# me433.net
KiCad netlist of a schematic drawn in EAGLE
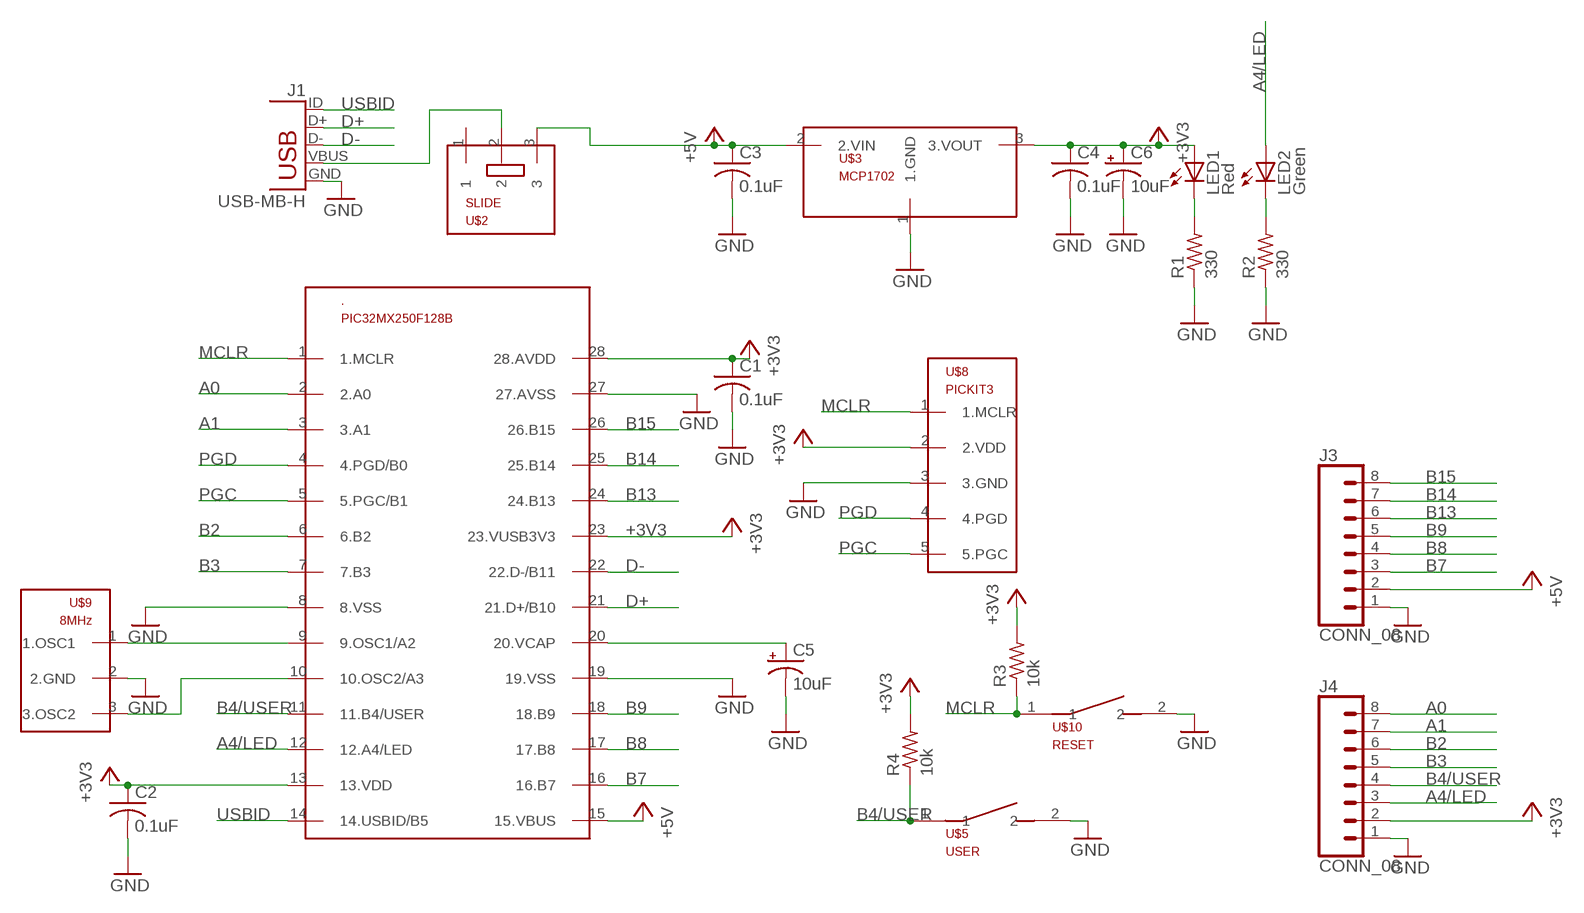
[diagram p0: schematic, sheet 1]

(export (version "E")
  (design (tool "Eeschema 10.0.6"))
  (components
    (comp (ref ".")
      (value "PIC32MX250F128B")
      (footprint "eagle-import:DIL28-3")
      (libsource (lib "eagle-import") (part "PIC32MX250F128B"))
    )
    (comp (ref "C1")
      (value "0.1uF")
      (footprint "eagle-import:C025-025X050")
      (libsource (lib "eagle-import") (part "C-US025-025X050"))
    )
    (comp (ref "C2")
      (value "0.1uF")
      (footprint "eagle-import:C025-025X050")
      (libsource (lib "eagle-import") (part "C-US025-025X050"))
    )
    (comp (ref "C3")
      (value "0.1uF")
      (footprint "eagle-import:C025-025X050")
      (libsource (lib "eagle-import") (part "C-US025-025X050"))
    )
    (comp (ref "C4")
      (value "0.1uF")
      (footprint "eagle-import:C025-025X050")
      (libsource (lib "eagle-import") (part "C-US025-025X050"))
    )
    (comp (ref "C5")
      (value "10uF")
      (footprint "eagle-import:B45181B")
      (libsource (lib "eagle-import") (part "CPOL-USB45181B"))
    )
    (comp (ref "C6")
      (value "10uF")
      (footprint "eagle-import:B45181B")
      (libsource (lib "eagle-import") (part "CPOL-USB45181B"))
    )
    (comp (ref "J1")
      (value "USB-MB-H")
      (footprint "eagle-import:USB-MB-H")
      (libsource (lib "eagle-import") (part "USB-MB-H"))
    )
    (comp (ref "J3")
      (value "CONN_08")
      (footprint "eagle-import:1X08")
      (libsource (lib "eagle-import") (part "CONN_08"))
    )
    (comp (ref "J4")
      (value "CONN_08")
      (footprint "eagle-import:1X08")
      (libsource (lib "eagle-import") (part "CONN_08"))
    )
    (comp (ref "LED1")
      (value "Red")
      (footprint "eagle-import:LED3MM")
      (libsource (lib "eagle-import") (part "LED3MM"))
    )
    (comp (ref "LED2")
      (value "Green")
      (footprint "eagle-import:LED3MM")
      (libsource (lib "eagle-import") (part "LED3MM"))
    )
    (comp (ref "R1")
      (value "330")
      (footprint "eagle-import:0207_10")
      (libsource (lib "eagle-import") (part "R-US_0207/10"))
    )
    (comp (ref "R2")
      (value "330")
      (footprint "eagle-import:0207_10")
      (libsource (lib "eagle-import") (part "R-US_0207/10"))
    )
    (comp (ref "R3")
      (value "10k")
      (footprint "eagle-import:0207_10")
      (libsource (lib "eagle-import") (part "R-US_0207/10"))
    )
    (comp (ref "R4")
      (value "10k")
      (footprint "eagle-import:0207_10")
      (libsource (lib "eagle-import") (part "R-US_0207/10"))
    )
    (comp (ref "U$2")
      (value "SLIDE")
      (footprint "eagle-import:SLIDE")
      (libsource (lib "eagle-import") (part "SLIDE"))
    )
    (comp (ref "U$3")
      (value "MCP1702")
      (footprint "eagle-import:TO92")
      (libsource (lib "eagle-import") (part "MCP1702"))
    )
    (comp (ref "U$5")
      (value "USER")
      (footprint "eagle-import:PB")
      (libsource (lib "eagle-import") (part "PB"))
    )
    (comp (ref "U$8")
      (value "PICKIT3")
      (footprint "eagle-import:1X05")
      (libsource (lib "eagle-import") (part "PICKIT3"))
    )
    (comp (ref "U$9")
      (value "8MHz")
      (footprint "eagle-import:OSC")
      (libsource (lib "eagle-import") (part "OSC"))
    )
    (comp (ref "U$10")
      (value "RESET")
      (footprint "eagle-import:PB")
      (libsource (lib "eagle-import") (part "PB"))
    )
  )
  (nets
    (net (code "1") (name "+3V3") (class "Default")
      (node (ref ".") (pin "13") (pinfunction "13.VDD_13") (pintype "bidirectional"))
      (node (ref ".") (pin "23") (pinfunction "23.VUSB3V3_23") (pintype "bidirectional"))
      (node (ref ".") (pin "28") (pinfunction "28.AVDD_28") (pintype "bidirectional"))
      (node (ref "C1") (pin "1") (pinfunction "1_1") (pintype "passive"))
      (node (ref "C2") (pin "1") (pinfunction "1_1") (pintype "passive"))
      (node (ref "C4") (pin "1") (pinfunction "1_1") (pintype "passive"))
      (node (ref "C6") (pin "+") (pinfunction "+_+") (pintype "passive"))
      (node (ref "J4") (pin "2") (pinfunction "2_2") (pintype "passive"))
      (node (ref "LED1") (pin "A") (pinfunction "A_A") (pintype "passive"))
      (node (ref "R3") (pin "2") (pinfunction "2_2") (pintype "passive"))
      (node (ref "R4") (pin "2") (pinfunction "2_2") (pintype "passive"))
      (node (ref "U$3") (pin "3") (pinfunction "3.VOUT_3") (pintype "bidirectional"))
      (node (ref "U$8") (pin "2") (pinfunction "2.VDD_2") (pintype "bidirectional"))
    )
    (net (code "2") (name "+5V") (class "Default")
      (node (ref ".") (pin "15") (pinfunction "15.VBUS_15") (pintype "bidirectional"))
      (node (ref "C3") (pin "1") (pinfunction "1_1") (pintype "passive"))
      (node (ref "J3") (pin "2") (pinfunction "2_2") (pintype "passive"))
      (node (ref "U$2") (pin "3") (pinfunction "3_3") (pintype "bidirectional"))
      (node (ref "U$3") (pin "2") (pinfunction "2.VIN_2") (pintype "bidirectional"))
    )
    (net (code "3") (name "/A0") (class "Default")
      (node (ref ".") (pin "2") (pinfunction "2.A0_2") (pintype "bidirectional"))
      (node (ref "J4") (pin "8") (pinfunction "8_8") (pintype "passive"))
    )
    (net (code "4") (name "/A1") (class "Default")
      (node (ref ".") (pin "3") (pinfunction "3.A1_3") (pintype "bidirectional"))
      (node (ref "J4") (pin "7") (pinfunction "7_7") (pintype "passive"))
    )
    (net (code "5") (name "/A4{slash}LED") (class "Default")
      (node (ref ".") (pin "12") (pinfunction "12.A4/LED_12") (pintype "bidirectional"))
      (node (ref "J4") (pin "3") (pinfunction "3_3") (pintype "passive"))
      (node (ref "LED2") (pin "A") (pinfunction "A_A") (pintype "passive"))
    )
    (net (code "6") (name "/B2") (class "Default")
      (node (ref ".") (pin "6") (pinfunction "6.B2_6") (pintype "bidirectional"))
      (node (ref "J4") (pin "6") (pinfunction "6_6") (pintype "passive"))
    )
    (net (code "7") (name "/B3") (class "Default")
      (node (ref ".") (pin "7") (pinfunction "7.B3_7") (pintype "bidirectional"))
      (node (ref "J4") (pin "5") (pinfunction "5_5") (pintype "passive"))
    )
    (net (code "8") (name "/B4{slash}USER") (class "Default")
      (node (ref ".") (pin "11") (pinfunction "11.B4/USER_11") (pintype "bidirectional"))
      (node (ref "J4") (pin "4") (pinfunction "4_4") (pintype "passive"))
      (node (ref "R4") (pin "1") (pinfunction "1_1") (pintype "passive"))
      (node (ref "U$5") (pin "1") (pinfunction "1_1") (pintype "bidirectional"))
    )
    (net (code "9") (name "/B7") (class "Default")
      (node (ref ".") (pin "16") (pinfunction "16.B7_16") (pintype "bidirectional"))
      (node (ref "J3") (pin "3") (pinfunction "3_3") (pintype "passive"))
    )
    (net (code "10") (name "/B8") (class "Default")
      (node (ref ".") (pin "17") (pinfunction "17.B8_17") (pintype "bidirectional"))
      (node (ref "J3") (pin "4") (pinfunction "4_4") (pintype "passive"))
    )
    (net (code "11") (name "/B9") (class "Default")
      (node (ref ".") (pin "18") (pinfunction "18.B9_18") (pintype "bidirectional"))
      (node (ref "J3") (pin "5") (pinfunction "5_5") (pintype "passive"))
    )
    (net (code "12") (name "/B13") (class "Default")
      (node (ref ".") (pin "24") (pinfunction "24.B13_24") (pintype "bidirectional"))
      (node (ref "J3") (pin "6") (pinfunction "6_6") (pintype "passive"))
    )
    (net (code "13") (name "/B14") (class "Default")
      (node (ref ".") (pin "25") (pinfunction "25.B14_25") (pintype "bidirectional"))
      (node (ref "J3") (pin "7") (pinfunction "7_7") (pintype "passive"))
    )
    (net (code "14") (name "/B15") (class "Default")
      (node (ref ".") (pin "26") (pinfunction "26.B15_26") (pintype "bidirectional"))
      (node (ref "J3") (pin "8") (pinfunction "8_8") (pintype "passive"))
    )
    (net (code "15") (name "/D+") (class "Default")
      (node (ref ".") (pin "21") (pinfunction "21.D+/B10_21") (pintype "bidirectional"))
      (node (ref "J1") (pin "D+") (pinfunction "D+_D+") (pintype "bidirectional"))
    )
    (net (code "16") (name "/D-") (class "Default")
      (node (ref ".") (pin "22") (pinfunction "22.D-/B11_22") (pintype "bidirectional"))
      (node (ref "J1") (pin "D-") (pinfunction "D-_D-") (pintype "bidirectional"))
    )
    (net (code "17") (name "/MCLR") (class "Default")
      (node (ref ".") (pin "1") (pinfunction "1.MCLR_1") (pintype "bidirectional"))
      (node (ref "R3") (pin "1") (pinfunction "1_1") (pintype "passive"))
      (node (ref "U$10") (pin "1") (pinfunction "1_1") (pintype "bidirectional"))
      (node (ref "U$8") (pin "1") (pinfunction "1.MCLR_1") (pintype "bidirectional"))
    )
    (net (code "18") (name "/PGC") (class "Default")
      (node (ref ".") (pin "5") (pinfunction "5.PGC/B1_5") (pintype "bidirectional"))
      (node (ref "U$8") (pin "5") (pinfunction "5.PGC_5") (pintype "bidirectional"))
    )
    (net (code "19") (name "/PGD") (class "Default")
      (node (ref ".") (pin "4") (pinfunction "4.PGD/B0_4") (pintype "bidirectional"))
      (node (ref "U$8") (pin "4") (pinfunction "4.PGD_4") (pintype "bidirectional"))
    )
    (net (code "20") (name "/USBID") (class "Default")
      (node (ref ".") (pin "14") (pinfunction "14.USBID/B5_14") (pintype "bidirectional"))
      (node (ref "J1") (pin "ID") (pinfunction "ID_ID") (pintype "bidirectional"))
    )
    (net (code "21") (name "GND") (class "Default")
      (node (ref ".") (pin "19") (pinfunction "19.VSS_19") (pintype "bidirectional"))
      (node (ref ".") (pin "27") (pinfunction "27.AVSS_27") (pintype "bidirectional"))
      (node (ref ".") (pin "8") (pinfunction "8.VSS_8") (pintype "bidirectional"))
      (node (ref "C1") (pin "2") (pinfunction "2_2") (pintype "passive"))
      (node (ref "C2") (pin "2") (pinfunction "2_2") (pintype "passive"))
      (node (ref "C3") (pin "2") (pinfunction "2_2") (pintype "passive"))
      (node (ref "C4") (pin "2") (pinfunction "2_2") (pintype "passive"))
      (node (ref "C5") (pin "-") (pinfunction "-_-") (pintype "passive"))
      (node (ref "C6") (pin "-") (pinfunction "-_-") (pintype "passive"))
      (node (ref "J1") (pin "GND") (pinfunction "GND_GND") (pintype "bidirectional"))
      (node (ref "J3") (pin "1") (pinfunction "1_1") (pintype "passive"))
      (node (ref "J4") (pin "1") (pinfunction "1_1") (pintype "passive"))
      (node (ref "R1") (pin "1") (pinfunction "1_1") (pintype "passive"))
      (node (ref "R2") (pin "1") (pinfunction "1_1") (pintype "passive"))
      (node (ref "U$10") (pin "2") (pinfunction "2_2") (pintype "bidirectional"))
      (node (ref "U$3") (pin "1") (pinfunction "1.GND_1") (pintype "bidirectional"))
      (node (ref "U$5") (pin "2") (pinfunction "2_2") (pintype "bidirectional"))
      (node (ref "U$8") (pin "3") (pinfunction "3.GND_3") (pintype "bidirectional"))
      (node (ref "U$9") (pin "2") (pinfunction "2.GND_2") (pintype "bidirectional"))
    )
    (net (code "22") (name "Net-(.-9.OSC1{slash}A2)") (class "Default")
      (node (ref ".") (pin "9") (pinfunction "9.OSC1/A2_9") (pintype "bidirectional"))
      (node (ref "U$9") (pin "1") (pinfunction "1.OSC1_1") (pintype "bidirectional"))
    )
    (net (code "23") (name "Net-(.-10.OSC2{slash}A3)") (class "Default")
      (node (ref ".") (pin "10") (pinfunction "10.OSC2/A3_10") (pintype "bidirectional"))
      (node (ref "U$9") (pin "3") (pinfunction "3.OSC2_3") (pintype "bidirectional"))
    )
    (net (code "24") (name "Net-(.-20.VCAP)") (class "Default")
      (node (ref ".") (pin "20") (pinfunction "20.VCAP_20") (pintype "bidirectional"))
      (node (ref "C5") (pin "+") (pinfunction "+_+") (pintype "passive"))
    )
    (net (code "25") (name "Net-(J1-PadVBUS)") (class "Default")
      (node (ref "J1") (pin "VBUS") (pinfunction "VBUS_VBUS") (pintype "bidirectional"))
      (node (ref "U$2") (pin "2") (pinfunction "2_2") (pintype "bidirectional"))
    )
    (net (code "26") (name "Net-(LED1-C)") (class "Default")
      (node (ref "LED1") (pin "K") (pinfunction "C_K") (pintype "passive"))
      (node (ref "R1") (pin "2") (pinfunction "2_2") (pintype "passive"))
    )
    (net (code "27") (name "Net-(LED2-C)") (class "Default")
      (node (ref "LED2") (pin "K") (pinfunction "C_K") (pintype "passive"))
      (node (ref "R2") (pin "2") (pinfunction "2_2") (pintype "passive"))
    )
    (net (code "28") (name "unconnected-(U$2-Pad1)") (class "Default")
      (node (ref "U$2") (pin "1") (pinfunction "1_1") (pintype "bidirectional"))
    )
  )
)
